# draft4-modular-split.net
KiCad netlist of a schematic drawn in EAGLE
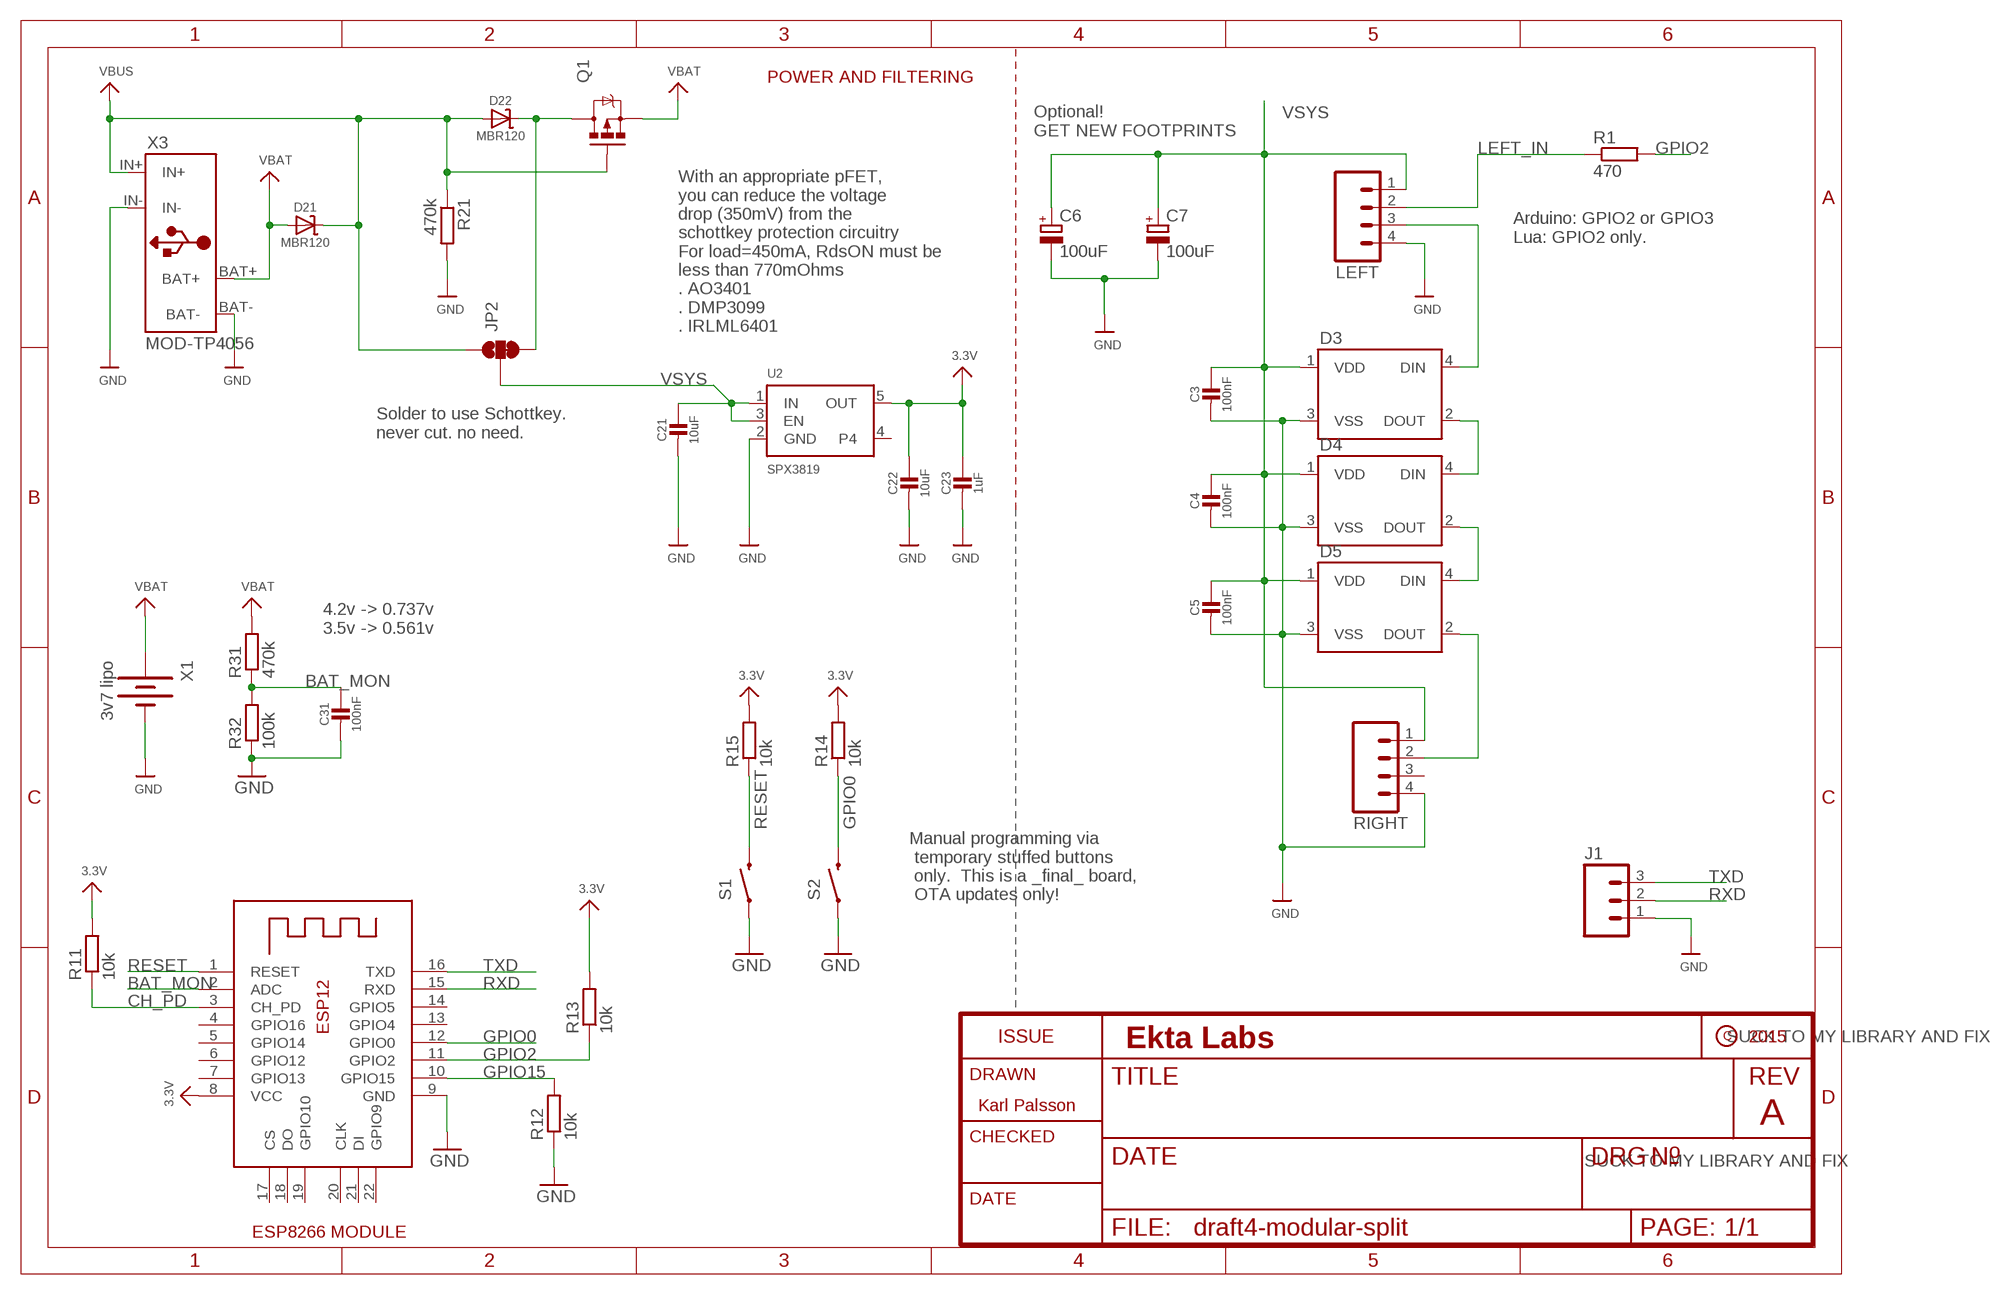
[diagram p0: schematic, sheet 1]

(export (version "E")
  (design (tool "Eeschema 10.0.6"))
  (components
    (comp (ref "C3")
      (value "100nF")
      (footprint "eagle-import:0805-NO")
      (libsource (lib "eagle-import") (part "CAP_CERAMIC0805-NOOUTLINE"))
    )
    (comp (ref "C4")
      (value "100nF")
      (footprint "eagle-import:0805-NO")
      (libsource (lib "eagle-import") (part "CAP_CERAMIC0805-NOOUTLINE"))
    )
    (comp (ref "C5")
      (value "100nF")
      (footprint "eagle-import:0805-NO")
      (libsource (lib "eagle-import") (part "CAP_CERAMIC0805-NOOUTLINE"))
    )
    (comp (ref "C6")
      (value "100uF")
      (footprint "eagle-import:PANASONIC_B")
      (libsource (lib "eagle-import") (part "CPOL-EUB"))
    )
    (comp (ref "C7")
      (value "100uF")
      (footprint "eagle-import:PANASONIC_B")
      (libsource (lib "eagle-import") (part "CPOL-EUB"))
    )
    (comp (ref "C21")
      (value "10uF")
      (footprint "eagle-import:0805-NO")
      (libsource (lib "eagle-import") (part "CAP_CERAMIC0805-NOOUTLINE"))
    )
    (comp (ref "C22")
      (value "10uF")
      (footprint "eagle-import:0805-NO")
      (libsource (lib "eagle-import") (part "CAP_CERAMIC0805-NOOUTLINE"))
    )
    (comp (ref "C23")
      (value "1uF")
      (footprint "eagle-import:0805-NO")
      (libsource (lib "eagle-import") (part "CAP_CERAMIC0805-NOOUTLINE"))
    )
    (comp (ref "C31")
      (value "100nF")
      (footprint "eagle-import:0805-NO")
      (libsource (lib "eagle-import") (part "CAP_CERAMIC0805-NOOUTLINE"))
    )
    (comp (ref "D3")
      (value "WS2812B")
      (footprint "eagle-import:WS2812B")
      (libsource (lib "eagle-import") (part "WS2812B"))
    )
    (comp (ref "D4")
      (value "WS2812B")
      (footprint "eagle-import:WS2812B")
      (libsource (lib "eagle-import") (part "WS2812B"))
    )
    (comp (ref "D5")
      (value "WS2812B")
      (footprint "eagle-import:WS2812B")
      (libsource (lib "eagle-import") (part "WS2812B"))
    )
    (comp (ref "D21")
      (value "MBR120")
      (footprint "eagle-import:SOD-123")
      (libsource (lib "eagle-import") (part "DIODE-SCHOTTKYSOD-123"))
    )
    (comp (ref "D22")
      (value "MBR120")
      (footprint "eagle-import:SOD-123")
      (libsource (lib "eagle-import") (part "DIODE-SCHOTTKYSOD-123"))
    )
    (comp (ref "J1")
      (value "M031X03_NO_SILK")
      (footprint "eagle-import:1X03_NO_SILK")
      (libsource (lib "eagle-import") (part "M031X03_NO_SILK"))
    )
    (comp (ref "JP2")
      (value "JUMPER-PAD-3-2OF3_NC_BY_TRACE_LARGE")
      (footprint "eagle-import:PAD-JUMPER-3-2OF3_NC_BY_TRACE_YES_SILK_LARGE")
      (libsource (lib "eagle-import") (part "JUMPER-PAD-3-2OF3_NC_BY_TRACE_LARGE"))
    )
    (comp (ref "LEFT")
      (value "M041X04_NO_SILK")
      (footprint "eagle-import:1X04_NO_SILK")
      (libsource (lib "eagle-import") (part "M041X04_NO_SILK"))
    )
    (comp (ref "Q1")
      (value "MOSFET-PCHANNEL")
      (footprint "eagle-import:SOT23-3")
      (libsource (lib "eagle-import") (part "MOSFET-PCHANNEL"))
    )
    (comp (ref "R1")
      (value "470")
      (footprint "eagle-import:R0603")
      (libsource (lib "eagle-import") (part "R-EU_R0603"))
    )
    (comp (ref "R11")
      (value "10k")
      (footprint "eagle-import:R0603")
      (libsource (lib "eagle-import") (part "R-EU_R0603"))
    )
    (comp (ref "R12")
      (value "10k")
      (footprint "eagle-import:R0603")
      (libsource (lib "eagle-import") (part "R-EU_R0603"))
    )
    (comp (ref "R13")
      (value "10k")
      (footprint "eagle-import:R0603")
      (libsource (lib "eagle-import") (part "R-EU_R0603"))
    )
    (comp (ref "R14")
      (value "10k")
      (footprint "eagle-import:R0603")
      (libsource (lib "eagle-import") (part "R-EU_R0603"))
    )
    (comp (ref "R15")
      (value "10k")
      (footprint "eagle-import:R0603")
      (libsource (lib "eagle-import") (part "R-EU_R0603"))
    )
    (comp (ref "R21")
      (value "470k")
      (footprint "eagle-import:R0603")
      (libsource (lib "eagle-import") (part "R-EU_R0603"))
    )
    (comp (ref "R31")
      (value "470k")
      (footprint "eagle-import:R0603")
      (libsource (lib "eagle-import") (part "R-EU_R0603"))
    )
    (comp (ref "R32")
      (value "100k")
      (footprint "eagle-import:R0603")
      (libsource (lib "eagle-import") (part "R-EU_R0603"))
    )
    (comp (ref "RIGHT")
      (value "M041X04_NO_SILK")
      (footprint "eagle-import:1X04_NO_SILK")
      (libsource (lib "eagle-import") (part "M041X04_NO_SILK"))
    )
    (comp (ref "S1")
      (value "SWITCH-MOMENTARY-2PTH")
      (footprint "eagle-import:TACTILE-PTH")
      (libsource (lib "eagle-import") (part "SWITCH-MOMENTARY-2PTH"))
    )
    (comp (ref "S2")
      (value "SWITCH-MOMENTARY-2PTH")
      (footprint "eagle-import:TACTILE-PTH")
      (libsource (lib "eagle-import") (part "SWITCH-MOMENTARY-2PTH"))
    )
    (comp (ref "U2")
      (value "SPX3819")
      (footprint "eagle-import:SOT23-5")
      (libsource (lib "eagle-import") (part "VREG_SOT23-5"))
    )
    (comp (ref "X1")
      (value "3v7 lipo")
      (footprint "eagle-import:BATT-18650-BLOSSOM-1")
      (libsource (lib "eagle-import") (part "BATTERY18650-BLOSSOM"))
    )
    (comp (ref "X2")
      (value "ESP-12")
      (footprint "eagle-import:ESP-12E")
      (libsource (lib "eagle-import") (part "ESP-12E"))
    )
    (comp (ref "X3")
      (value "MOD-TP4056")
      (footprint "eagle-import:MOD-LIPO_CHARGER")
      (libsource (lib "eagle-import") (part "MOD-LIPO_CHARGER"))
    )
  )
  (nets
    (net (code "1") (name "/BAT_MON") (class "Default")
      (node (ref "C31") (pin "1") (pinfunction "1_1") (pintype "passive"))
      (node (ref "R31") (pin "1") (pinfunction "1_1") (pintype "passive"))
      (node (ref "R32") (pin "2") (pinfunction "2_2") (pintype "passive"))
      (node (ref "X2") (pin "2") (pinfunction "ADC_2") (pintype "passive"))
    )
    (net (code "2") (name "/CH_PD") (class "Default")
      (node (ref "R11") (pin "1") (pinfunction "1_1") (pintype "passive"))
      (node (ref "X2") (pin "3") (pinfunction "CH_PD_3") (pintype "input"))
    )
    (net (code "3") (name "/GPIO0") (class "Default")
      (node (ref "R14") (pin "1") (pinfunction "1_1") (pintype "passive"))
      (node (ref "S2") (pin "3") (pinfunction "2_3") (pintype "passive"))
      (node (ref "X2") (pin "12") (pinfunction "GPIO0_12") (pintype "bidirectional"))
    )
    (net (code "4") (name "/GPIO2") (class "Default")
      (node (ref "R1") (pin "2") (pinfunction "2_2") (pintype "passive"))
      (node (ref "R13") (pin "1") (pinfunction "1_1") (pintype "passive"))
      (node (ref "X2") (pin "11") (pinfunction "GPIO2_11") (pintype "bidirectional"))
    )
    (net (code "5") (name "/GPIO15") (class "Default")
      (node (ref "R12") (pin "2") (pinfunction "2_2") (pintype "passive"))
      (node (ref "X2") (pin "10") (pinfunction "GPIO15_10") (pintype "bidirectional"))
    )
    (net (code "6") (name "/LEFT_IN") (class "Default")
      (node (ref "LEFT") (pin "2") (pinfunction "2_2") (pintype "passive"))
      (node (ref "R1") (pin "1") (pinfunction "1_1") (pintype "passive"))
    )
    (net (code "7") (name "/RESET") (class "Default")
      (node (ref "R15") (pin "1") (pinfunction "1_1") (pintype "passive"))
      (node (ref "S1") (pin "3") (pinfunction "2_3") (pintype "passive"))
      (node (ref "X2") (pin "1") (pinfunction "RESET_1") (pintype "input"))
    )
    (net (code "8") (name "/RXD") (class "Default")
      (node (ref "J1") (pin "2") (pinfunction "2_2") (pintype "passive"))
      (node (ref "X2") (pin "15") (pinfunction "RXD_15") (pintype "input"))
    )
    (net (code "9") (name "/TXD") (class "Default")
      (node (ref "J1") (pin "3") (pinfunction "3_3") (pintype "passive"))
      (node (ref "X2") (pin "16") (pinfunction "TXD_16") (pintype "output"))
    )
    (net (code "10") (name "/VSYS") (class "Default")
      (node (ref "C21") (pin "1") (pinfunction "1_1") (pintype "passive"))
      (node (ref "C3") (pin "1") (pinfunction "1_1") (pintype "passive"))
      (node (ref "C4") (pin "1") (pinfunction "1_1") (pintype "passive"))
      (node (ref "C5") (pin "1") (pinfunction "1_1") (pintype "passive"))
      (node (ref "C6") (pin "+") (pinfunction "+_+") (pintype "passive"))
      (node (ref "C7") (pin "+") (pinfunction "+_+") (pintype "passive"))
      (node (ref "D3") (pin "1") (pinfunction "VDD_1") (pintype "power_in"))
      (node (ref "D4") (pin "1") (pinfunction "VDD_1") (pintype "power_in"))
      (node (ref "D5") (pin "1") (pinfunction "VDD_1") (pintype "power_in"))
      (node (ref "JP2") (pin "2") (pinfunction "2_2") (pintype "passive"))
      (node (ref "LEFT") (pin "1") (pinfunction "1_1") (pintype "passive"))
      (node (ref "RIGHT") (pin "1") (pinfunction "1_1") (pintype "passive"))
      (node (ref "U2") (pin "1") (pinfunction "IN_1") (pintype "power_in"))
      (node (ref "U2") (pin "3") (pinfunction "EN_3") (pintype "input"))
    )
    (net (code "11") (name "3.3V") (class "Default")
      (node (ref "C22") (pin "1") (pinfunction "1_1") (pintype "passive"))
      (node (ref "C23") (pin "1") (pinfunction "1_1") (pintype "passive"))
      (node (ref "R11") (pin "2") (pinfunction "2_2") (pintype "passive"))
      (node (ref "R13") (pin "2") (pinfunction "2_2") (pintype "passive"))
      (node (ref "R14") (pin "2") (pinfunction "2_2") (pintype "passive"))
      (node (ref "R15") (pin "2") (pinfunction "2_2") (pintype "passive"))
      (node (ref "U2") (pin "5") (pinfunction "OUT_5") (pintype "power_in"))
      (node (ref "X2") (pin "8") (pinfunction "VCC_8") (pintype "power_in"))
    )
    (net (code "12") (name "GND") (class "Default")
      (node (ref "C21") (pin "2") (pinfunction "2_2") (pintype "passive"))
      (node (ref "C22") (pin "2") (pinfunction "2_2") (pintype "passive"))
      (node (ref "C23") (pin "2") (pinfunction "2_2") (pintype "passive"))
      (node (ref "C3") (pin "2") (pinfunction "2_2") (pintype "passive"))
      (node (ref "C31") (pin "2") (pinfunction "2_2") (pintype "passive"))
      (node (ref "C4") (pin "2") (pinfunction "2_2") (pintype "passive"))
      (node (ref "C5") (pin "2") (pinfunction "2_2") (pintype "passive"))
      (node (ref "C6") (pin "-") (pinfunction "-_-") (pintype "passive"))
      (node (ref "C7") (pin "-") (pinfunction "-_-") (pintype "passive"))
      (node (ref "D3") (pin "3") (pinfunction "VSS_3") (pintype "power_in"))
      (node (ref "D4") (pin "3") (pinfunction "VSS_3") (pintype "power_in"))
      (node (ref "D5") (pin "3") (pinfunction "VSS_3") (pintype "power_in"))
      (node (ref "J1") (pin "1") (pinfunction "1_1") (pintype "passive"))
      (node (ref "LEFT") (pin "4") (pinfunction "4_4") (pintype "passive"))
      (node (ref "R12") (pin "1") (pinfunction "1_1") (pintype "passive"))
      (node (ref "R21") (pin "2") (pinfunction "2_2") (pintype "passive"))
      (node (ref "R32") (pin "1") (pinfunction "1_1") (pintype "passive"))
      (node (ref "RIGHT") (pin "4") (pinfunction "4_4") (pintype "passive"))
      (node (ref "S1") (pin "1") (pinfunction "1_1") (pintype "passive"))
      (node (ref "S2") (pin "1") (pinfunction "1_1") (pintype "passive"))
      (node (ref "U2") (pin "2") (pinfunction "GND_2") (pintype "power_in"))
      (node (ref "X1") (pin "-") (pinfunction "-_-") (pintype "power_in"))
      (node (ref "X2") (pin "9") (pinfunction "GND_9") (pintype "power_in"))
      (node (ref "X3") (pin "BAT-") (pinfunction "BAT-_BAT-") (pintype "bidirectional"))
      (node (ref "X3") (pin "IN-") (pinfunction "IN-_IN-") (pintype "bidirectional"))
    )
    (net (code "13") (name "Net-(D3-DIN)") (class "Default")
      (node (ref "D3") (pin "4") (pinfunction "DIN_4") (pintype "input"))
      (node (ref "LEFT") (pin "3") (pinfunction "3_3") (pintype "passive"))
    )
    (net (code "14") (name "Net-(D3-DOUT)") (class "Default")
      (node (ref "D3") (pin "2") (pinfunction "DOUT_2") (pintype "output"))
      (node (ref "D4") (pin "4") (pinfunction "DIN_4") (pintype "input"))
    )
    (net (code "15") (name "Net-(D4-DOUT)") (class "Default")
      (node (ref "D4") (pin "2") (pinfunction "DOUT_2") (pintype "output"))
      (node (ref "D5") (pin "4") (pinfunction "DIN_4") (pintype "input"))
    )
    (net (code "16") (name "Net-(D5-DOUT)") (class "Default")
      (node (ref "D5") (pin "2") (pinfunction "DOUT_2") (pintype "output"))
      (node (ref "RIGHT") (pin "2") (pinfunction "2_2") (pintype "passive"))
    )
    (net (code "17") (name "Net-(Q1-D)") (class "Default")
      (node (ref "D22") (pin "C") (pinfunction "C_C") (pintype "passive"))
      (node (ref "JP2") (pin "3") (pinfunction "3_3") (pintype "passive"))
      (node (ref "Q1") (pin "3") (pinfunction "D_3") (pintype "passive"))
    )
    (net (code "18") (name "VBAT") (class "Default")
      (node (ref "D21") (pin "A") (pinfunction "A_A") (pintype "passive"))
      (node (ref "Q1") (pin "2") (pinfunction "S_2") (pintype "passive"))
      (node (ref "R31") (pin "2") (pinfunction "2_2") (pintype "passive"))
      (node (ref "X1") (pin "+") (pinfunction "+_+") (pintype "power_in"))
      (node (ref "X3") (pin "BAT+") (pinfunction "BAT+_BAT+") (pintype "bidirectional"))
    )
    (net (code "19") (name "VBUS") (class "Default")
      (node (ref "D21") (pin "C") (pinfunction "C_C") (pintype "passive"))
      (node (ref "D22") (pin "A") (pinfunction "A_A") (pintype "passive"))
      (node (ref "JP2") (pin "1") (pinfunction "1_1") (pintype "passive"))
      (node (ref "Q1") (pin "1") (pinfunction "G_1") (pintype "passive"))
      (node (ref "R21") (pin "1") (pinfunction "1_1") (pintype "passive"))
      (node (ref "X3") (pin "IN+") (pinfunction "IN+_IN+") (pintype "bidirectional"))
    )
    (net (code "20") (name "unconnected-(RIGHT-Pad3)") (class "Default")
      (node (ref "RIGHT") (pin "3") (pinfunction "3_3") (pintype "passive"))
    )
    (net (code "21") (name "unconnected-(U2-P4-Pad4)") (class "Default")
      (node (ref "U2") (pin "4") (pinfunction "P4_4") (pintype "bidirectional"))
    )
    (net (code "22") (name "unconnected-(X2-CLK-Pad20)") (class "Default")
      (node (ref "X2") (pin "20") (pinfunction "CLK_20") (pintype "bidirectional"))
    )
    (net (code "23") (name "unconnected-(X2-CS-Pad17)") (class "Default")
      (node (ref "X2") (pin "17") (pinfunction "CS_17") (pintype "bidirectional"))
    )
    (net (code "24") (name "unconnected-(X2-DI-Pad21)") (class "Default")
      (node (ref "X2") (pin "21") (pinfunction "DI_21") (pintype "bidirectional"))
    )
    (net (code "25") (name "unconnected-(X2-DO-Pad18)") (class "Default")
      (node (ref "X2") (pin "18") (pinfunction "DO_18") (pintype "bidirectional"))
    )
    (net (code "26") (name "unconnected-(X2-GPIO4-Pad13)") (class "Default")
      (node (ref "X2") (pin "13") (pinfunction "GPIO4_13") (pintype "bidirectional"))
    )
    (net (code "27") (name "unconnected-(X2-GPIO5-Pad14)") (class "Default")
      (node (ref "X2") (pin "14") (pinfunction "GPIO5_14") (pintype "bidirectional"))
    )
    (net (code "28") (name "unconnected-(X2-GPIO9-Pad22)") (class "Default")
      (node (ref "X2") (pin "22") (pinfunction "GPIO9_22") (pintype "bidirectional"))
    )
    (net (code "29") (name "unconnected-(X2-GPIO10-Pad19)") (class "Default")
      (node (ref "X2") (pin "19") (pinfunction "GPIO10_19") (pintype "bidirectional"))
    )
    (net (code "30") (name "unconnected-(X2-GPIO12-Pad6)") (class "Default")
      (node (ref "X2") (pin "6") (pinfunction "GPIO12_6") (pintype "bidirectional"))
    )
    (net (code "31") (name "unconnected-(X2-GPIO13-Pad7)") (class "Default")
      (node (ref "X2") (pin "7") (pinfunction "GPIO13_7") (pintype "bidirectional"))
    )
    (net (code "32") (name "unconnected-(X2-GPIO14-Pad5)") (class "Default")
      (node (ref "X2") (pin "5") (pinfunction "GPIO14_5") (pintype "bidirectional"))
    )
    (net (code "33") (name "unconnected-(X2-GPIO16-Pad4)") (class "Default")
      (node (ref "X2") (pin "4") (pinfunction "GPIO16_4") (pintype "bidirectional"))
    )
  )
)
